# 07_EL_CON.net
KiCad netlist of a schematic drawn in Altium Designer
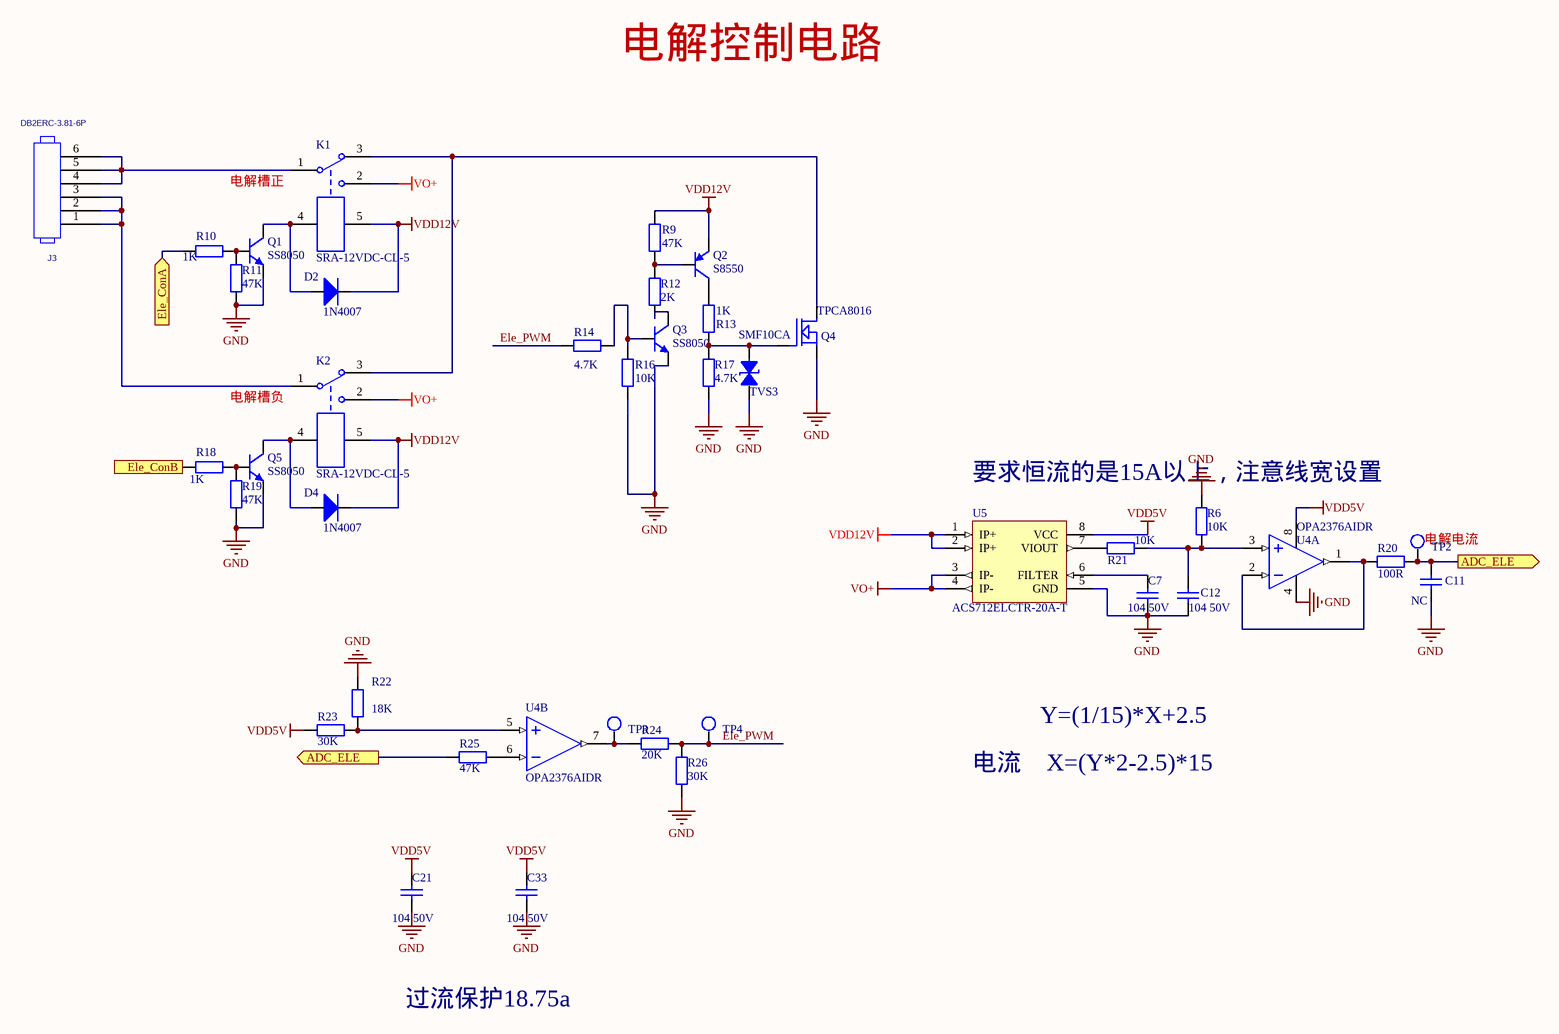
[diagram p0: 07_EL_CON.SchDoc]

(export (version "E")
  (design (tool "Eeschema 10.0.6"))
  (components
    (comp (ref "C7")
      (value "104 50V")
      (footprint "SMD-0603C")
      (description "贴片电容 10%")
      (libsource (lib "XiaoyI") (part "CAP4"))
    )
    (comp (ref "C11")
      (value "NC")
      (footprint "SMD-0603C")
      (description "贴片电容 10%")
      (libsource (lib "XiaoyI") (part "CAP4"))
    )
    (comp (ref "C12")
      (value "104 50V")
      (footprint "SMD-0603C")
      (description "贴片电容 10%")
      (libsource (lib "XiaoyI") (part "CAP4"))
    )
    (comp (ref "C21")
      (value "104 50V")
      (footprint "SMD-0603C")
      (description "贴片电容 20%")
      (libsource (lib "XiaoyI") (part "CAP4"))
    )
    (comp (ref "C33")
      (value "104 50V")
      (footprint "SMD-0603C")
      (description "贴片电容 20%")
      (libsource (lib "XiaoyI") (part "CAP4"))
    )
    (comp (ref "D2")
      (value "1N4007")
      (footprint "DO-214-AC")
      (description "贴片二极管")
      (libsource (lib "XiaoyI") (part "DIODE2"))
    )
    (comp (ref "D4")
      (value "1N4007")
      (footprint "DO-214-AC")
      (description "贴片二极管")
      (libsource (lib "XiaoyI") (part "DIODE2"))
    )
    (comp (ref "J3")
      (value "DB2ERC-3.81-6P")
      (footprint "DB2ERC-3P81-6P")
      (fields (field (name "Comment") "HEADER_6"))
      (libsource (lib "liujingtao_V1.0") (part "HEADER_6"))
    )
    (comp (ref "K1")
      (value "SRA-12VDC-CL-5")
      (footprint "SRA- 12V")
      (description "5V 继电器")
      (libsource (lib "XiaoyI") (part "JDQ1"))
    )
    (comp (ref "K2")
      (value "SRA-12VDC-CL-5")
      (footprint "SRA- 12V")
      (description "5V 继电器")
      (libsource (lib "XiaoyI") (part "JDQ1"))
    )
    (comp (ref "Q1")
      (value "SS8050")
      (footprint "SOT-23")
      (description "三极管")
      (libsource (lib "XiaoyI") (part "NPN-1"))
    )
    (comp (ref "Q2")
      (value "S8550")
      (footprint "SOT-23")
      (description "PNP")
      (libsource (lib "XiaoyI") (part "PNP"))
    )
    (comp (ref "Q3")
      (value "SS8050")
      (footprint "SOT-23")
      (description "三极管")
      (libsource (lib "XiaoyI") (part "NPN-1"))
    )
    (comp (ref "Q4") (value "TPCA8016") (footprint "DFN-8 5X6") (libsource (lib "POWER") (part "SI7860")))
    (comp (ref "Q5")
      (value "SS8050")
      (footprint "SOT-23")
      (description "三极管")
      (libsource (lib "XiaoyI") (part "NPN-1"))
    )
    (comp (ref "R6")
      (value "10K")
      (footprint "SMD-0603")
      (description "贴片电阻 1%")
      (libsource (lib "") (part "RES0_1"))
    )
    (comp (ref "R9")
      (value "47K")
      (footprint "SMD-0603")
      (description "贴片电阻 5%")
      (libsource (lib "") (part "RES-SOP_2"))
    )
    (comp (ref "R10")
      (value "1K")
      (footprint "SMD-0603")
      (description "贴片电阻 5%")
      (libsource (lib "XiaoyI") (part "RES2"))
    )
    (comp (ref "R11")
      (value "47K")
      (footprint "SMD-0603")
      (description "贴片电阻 5%")
      (libsource (lib "") (part "RES2_1"))
    )
    (comp (ref "R12")
      (value "2K")
      (footprint "SMD-0603")
      (description "贴片电阻 5%")
      (libsource (lib "") (part "RES-SOP_1"))
    )
    (comp (ref "R13")
      (value "1K")
      (footprint "SMD-0603")
      (description "贴片电阻 5%")
      (libsource (lib "") (part "RES-SOP_2"))
    )
    (comp (ref "R14")
      (value "4.7K")
      (footprint "SMD-0603")
      (description "贴片电阻 5%")
      (libsource (lib "XiaoyI") (part "RES-SOP"))
    )
    (comp (ref "R16")
      (value "10K")
      (footprint "SMD-0603")
      (description "贴片电阻 5%")
      (libsource (lib "") (part "RES-SOP_2"))
    )
    (comp (ref "R17")
      (value "4.7K")
      (footprint "SMD-0603")
      (description "贴片电阻 5%")
      (libsource (lib "") (part "RES-SOP_1"))
    )
    (comp (ref "R18")
      (value "1K")
      (footprint "SMD-0603")
      (description "贴片电阻 5%")
      (libsource (lib "XiaoyI") (part "RES2"))
    )
    (comp (ref "R19")
      (value "47K")
      (footprint "SMD-0603")
      (description "贴片电阻 5%")
      (libsource (lib "") (part "RES2_1"))
    )
    (comp (ref "R20")
      (value "100R")
      (footprint "SMD-0603")
      (description "贴片电阻 5%")
      (libsource (lib "ABB") (part "RES0"))
    )
    (comp (ref "R21")
      (value "10K")
      (footprint "SMD-0603")
      (description "贴片电阻 1%")
      (libsource (lib "ABB") (part "RES0"))
    )
    (comp (ref "R22")
      (value "18K")
      (footprint "SMD-0603")
      (description "贴片电阻 5%")
      (libsource (lib "") (part "RES-SOP_2"))
    )
    (comp (ref "R23")
      (value "30K")
      (footprint "SMD-0603")
      (description "贴片电阻 5%")
      (libsource (lib "XiaoyI") (part "RES-SOP"))
    )
    (comp (ref "R24")
      (value "20K")
      (footprint "SMD-0603")
      (description "贴片电阻 5%")
      (libsource (lib "XiaoyI") (part "RES-SOP"))
    )
    (comp (ref "R25")
      (value "47K")
      (footprint "SMD-0603")
      (description "贴片电阻 5%")
      (libsource (lib "XiaoyI") (part "RES-SOP"))
    )
    (comp (ref "R26")
      (value "30K")
      (footprint "SMD-0603")
      (description "贴片电阻 5%")
      (libsource (lib "") (part "RES-SOP_1"))
    )
    (comp (ref "TP2") (value "TPS") (footprint "tpd") (libsource (lib "stm32") (part "TPS")))
    (comp (ref "TP3") (value "TPS") (footprint "tpd") (libsource (lib "stm32") (part "TPS")))
    (comp (ref "TP4") (value "TPS") (footprint "tpd") (libsource (lib "stm32") (part "TPS")))
    (comp (ref "TVS3")
      (value "SMF10CA")
      (footprint "SOD-123")
      (description "TVS 10V")
      (libsource (lib "XiaoyI") (part "TVS-1"))
    )
    (comp (ref "U4")
      (value "OPA2376AIDR")
      (footprint "SOIC-8")
      (description "运算放大器")
      (libsource (lib "XiaoyI") (part "LM358"))
    )
    (comp (ref "U5")
      (value "ACS712ELCTR-20A-T")
      (footprint "SO-8")
      (description "HALL 20A 电流传感器")
      (libsource (lib "XiaoyI") (part "ACS712"))
    )
  )
  (nets
    (net (code "1") (name "/ADC_ELE") (class "Default")
      (node (ref "C11") (pin "2") (pinfunction "2_2") (pintype "passive"))
      (node (ref "R20") (pin "1") (pinfunction "1_1") (pintype "passive"))
      (node (ref "R25") (pin "2") (pinfunction "2_2") (pintype "passive"))
      (node (ref "TP2") (pin "1") (pinfunction "1_1") (pintype "passive"))
    )
    (net (code "2") (name "/Ele_ConA") (class "Default")
      (node (ref "R10") (pin "1") (pinfunction "1_1") (pintype "passive"))
    )
    (net (code "3") (name "/Ele_ConB") (class "Default")
      (node (ref "R18") (pin "1") (pinfunction "1_1") (pintype "passive"))
    )
    (net (code "4") (name "/Ele_PWM") (class "Default")
      (node (ref "R14") (pin "2") (pinfunction "2_2") (pintype "passive"))
      (node (ref "R24") (pin "1") (pinfunction "1_1") (pintype "passive"))
      (node (ref "R26") (pin "1") (pinfunction "1_1") (pintype "passive"))
      (node (ref "TP4") (pin "1") (pinfunction "1_1") (pintype "passive"))
    )
    (net (code "5") (name "GND") (class "Default")
      (node (ref "C11") (pin "1") (pinfunction "1_1") (pintype "passive"))
      (node (ref "C12") (pin "2") (pinfunction "2_2") (pintype "passive"))
      (node (ref "C21") (pin "1") (pinfunction "1_1") (pintype "passive"))
      (node (ref "C33") (pin "1") (pinfunction "1_1") (pintype "passive"))
      (node (ref "C7") (pin "2") (pinfunction "2_2") (pintype "passive"))
      (node (ref "Q1") (pin "2") (pinfunction "E_2") (pintype "passive"))
      (node (ref "Q3") (pin "2") (pinfunction "E_2") (pintype "passive"))
      (node (ref "Q4") (pin "3") (pinfunction "S_3") (pintype "passive"))
      (node (ref "Q5") (pin "2") (pinfunction "E_2") (pintype "passive"))
      (node (ref "R11") (pin "1") (pinfunction "1_1") (pintype "passive"))
      (node (ref "R16") (pin "1") (pinfunction "1_1") (pintype "passive"))
      (node (ref "R17") (pin "2") (pinfunction "2_2") (pintype "passive"))
      (node (ref "R19") (pin "1") (pinfunction "1_1") (pintype "passive"))
      (node (ref "R22") (pin "2") (pinfunction "2_2") (pintype "passive"))
      (node (ref "R26") (pin "2") (pinfunction "2_2") (pintype "passive"))
      (node (ref "R6") (pin "1") (pinfunction "1_1") (pintype "passive"))
      (node (ref "TVS3") (pin "1") (pinfunction "A_1") (pintype "passive"))
      (node (ref "U4") (pin "4") (pinfunction "V-_4") (pintype "power_in"))
      (node (ref "U5") (pin "5") (pinfunction "GND_5") (pintype "power_in"))
    )
    (net (code "6") (name "Net-(D2-A)") (class "Default")
      (node (ref "D2") (pin "1") (pinfunction "A_1") (pintype "passive"))
      (node (ref "K1") (pin "4") (pinfunction "4_4") (pintype "passive"))
      (node (ref "Q1") (pin "3") (pinfunction "C_3") (pintype "passive"))
    )
    (net (code "7") (name "Net-(D4-A)") (class "Default")
      (node (ref "D4") (pin "1") (pinfunction "A_1") (pintype "passive"))
      (node (ref "K2") (pin "4") (pinfunction "4_4") (pintype "passive"))
      (node (ref "Q5") (pin "3") (pinfunction "C_3") (pintype "passive"))
    )
    (net (code "8") (name "Net-(J3-Pad1)") (class "Default")
      (node (ref "J3") (pin "1") (pinfunction "1_1") (pintype "passive"))
      (node (ref "J3") (pin "2") (pinfunction "2_2") (pintype "passive"))
      (node (ref "J3") (pin "3") (pinfunction "3_3") (pintype "passive"))
      (node (ref "K2") (pin "1") (pinfunction "1_1") (pintype "passive"))
    )
    (net (code "9") (name "Net-(J3-Pad4)") (class "Default")
      (node (ref "J3") (pin "4") (pinfunction "4_4") (pintype "passive"))
      (node (ref "J3") (pin "5") (pinfunction "5_5") (pintype "passive"))
      (node (ref "J3") (pin "6") (pinfunction "6_6") (pintype "passive"))
      (node (ref "K1") (pin "1") (pinfunction "1_1") (pintype "passive"))
    )
    (net (code "10") (name "Net-(Q1-B)") (class "Default")
      (node (ref "Q1") (pin "1") (pinfunction "B_1") (pintype "passive"))
      (node (ref "R10") (pin "2") (pinfunction "2_2") (pintype "passive"))
      (node (ref "R11") (pin "2") (pinfunction "2_2") (pintype "passive"))
    )
    (net (code "11") (name "Net-(Q2-B)") (class "Default")
      (node (ref "Q2") (pin "1") (pinfunction "B_1") (pintype "passive"))
      (node (ref "R12") (pin "1") (pinfunction "1_1") (pintype "passive"))
      (node (ref "R9") (pin "1") (pinfunction "1_1") (pintype "passive"))
    )
    (net (code "12") (name "Net-(Q2-C)") (class "Default")
      (node (ref "Q2") (pin "3") (pinfunction "C_3") (pintype "passive"))
      (node (ref "R13") (pin "2") (pinfunction "2_2") (pintype "passive"))
    )
    (net (code "13") (name "Net-(Q3-B)") (class "Default")
      (node (ref "Q3") (pin "1") (pinfunction "B_1") (pintype "passive"))
      (node (ref "R14") (pin "1") (pinfunction "1_1") (pintype "passive"))
      (node (ref "R16") (pin "2") (pinfunction "2_2") (pintype "passive"))
    )
    (net (code "14") (name "Net-(Q3-C)") (class "Default")
      (node (ref "Q3") (pin "3") (pinfunction "C_3") (pintype "passive"))
      (node (ref "R12") (pin "2") (pinfunction "2_2") (pintype "passive"))
    )
    (net (code "15") (name "Net-(Q4-D)") (class "Default")
      (node (ref "K1") (pin "3") (pinfunction "3_3") (pintype "passive"))
      (node (ref "K2") (pin "3") (pinfunction "3_3") (pintype "passive"))
      (node (ref "Q4") (pin "2") (pinfunction "D_2") (pintype "passive"))
    )
    (net (code "16") (name "Net-(Q4-G)") (class "Default")
      (node (ref "Q4") (pin "1") (pinfunction "G_1") (pintype "passive"))
      (node (ref "R13") (pin "1") (pinfunction "1_1") (pintype "passive"))
      (node (ref "R17") (pin "1") (pinfunction "1_1") (pintype "passive"))
      (node (ref "TVS3") (pin "2") (pinfunction "B_2") (pintype "passive"))
    )
    (net (code "17") (name "Net-(Q5-B)") (class "Default")
      (node (ref "Q5") (pin "1") (pinfunction "B_1") (pintype "passive"))
      (node (ref "R18") (pin "2") (pinfunction "2_2") (pintype "passive"))
      (node (ref "R19") (pin "2") (pinfunction "2_2") (pintype "passive"))
    )
    (net (code "18") (name "Net-(U4A-IN1+)") (class "Default")
      (node (ref "C12") (pin "1") (pinfunction "1_1") (pintype "passive"))
      (node (ref "R21") (pin "1") (pinfunction "1_1") (pintype "passive"))
      (node (ref "R6") (pin "2") (pinfunction "2_2") (pintype "passive"))
      (node (ref "U4") (pin "3") (pinfunction "IN1+_3") (pintype "input"))
    )
    (net (code "19") (name "Net-(U4A-IN1-)") (class "Default")
      (node (ref "R20") (pin "2") (pinfunction "2_2") (pintype "passive"))
      (node (ref "U4") (pin "1") (pinfunction "OUT1_1") (pintype "output"))
      (node (ref "U4") (pin "2") (pinfunction "IN1-_2") (pintype "input"))
    )
    (net (code "20") (name "Net-(U4B-IN2+)") (class "Default")
      (node (ref "R22") (pin "1") (pinfunction "1_1") (pintype "passive"))
      (node (ref "R23") (pin "1") (pinfunction "1_1") (pintype "passive"))
      (node (ref "U4") (pin "5") (pinfunction "IN2+_5") (pintype "input"))
    )
    (net (code "21") (name "Net-(U4B-IN2-)") (class "Default")
      (node (ref "R25") (pin "1") (pinfunction "1_1") (pintype "passive"))
      (node (ref "U4") (pin "6") (pinfunction "IN2-_6") (pintype "input"))
    )
    (net (code "22") (name "Net-(U4B-OUT2)") (class "Default")
      (node (ref "R24") (pin "2") (pinfunction "2_2") (pintype "passive"))
      (node (ref "TP3") (pin "1") (pinfunction "1_1") (pintype "passive"))
      (node (ref "U4") (pin "7") (pinfunction "OUT2_7") (pintype "output"))
    )
    (net (code "23") (name "Net-(U5-FILTER)") (class "Default")
      (node (ref "C7") (pin "1") (pinfunction "1_1") (pintype "passive"))
      (node (ref "U5") (pin "6") (pinfunction "FILTER_6") (pintype "input"))
    )
    (net (code "24") (name "Net-(U5-VIOUT)") (class "Default")
      (node (ref "R21") (pin "2") (pinfunction "2_2") (pintype "passive"))
      (node (ref "U5") (pin "7") (pinfunction "VIOUT_7") (pintype "output"))
    )
    (net (code "25") (name "VDD5V") (class "Default")
      (node (ref "C21") (pin "2") (pinfunction "2_2") (pintype "passive"))
      (node (ref "C33") (pin "2") (pinfunction "2_2") (pintype "passive"))
      (node (ref "R23") (pin "2") (pinfunction "2_2") (pintype "passive"))
      (node (ref "U4") (pin "8") (pinfunction "V+_8") (pintype "power_in"))
      (node (ref "U5") (pin "8") (pinfunction "VCC_8") (pintype "power_in"))
    )
    (net (code "26") (name "VDD12V") (class "Default")
      (node (ref "D2") (pin "2") (pinfunction "K_2") (pintype "passive"))
      (node (ref "D4") (pin "2") (pinfunction "K_2") (pintype "passive"))
      (node (ref "K1") (pin "5") (pinfunction "5_5") (pintype "passive"))
      (node (ref "K2") (pin "5") (pinfunction "5_5") (pintype "passive"))
      (node (ref "Q2") (pin "2") (pinfunction "E_2") (pintype "passive"))
      (node (ref "R9") (pin "2") (pinfunction "2_2") (pintype "passive"))
      (node (ref "U5") (pin "1") (pinfunction "IP+_1") (pintype "input"))
      (node (ref "U5") (pin "2") (pinfunction "IP+_2") (pintype "input"))
    )
    (net (code "27") (name "VO+") (class "Default")
      (node (ref "K1") (pin "2") (pinfunction "2_2") (pintype "passive"))
      (node (ref "K2") (pin "2") (pinfunction "2_2") (pintype "passive"))
      (node (ref "U5") (pin "3") (pinfunction "IP-_3") (pintype "output"))
      (node (ref "U5") (pin "4") (pinfunction "IP-_4") (pintype "output"))
    )
  )
)
